# schematic_01.net
KiCad netlist of a schematic drawn in Altium Designer
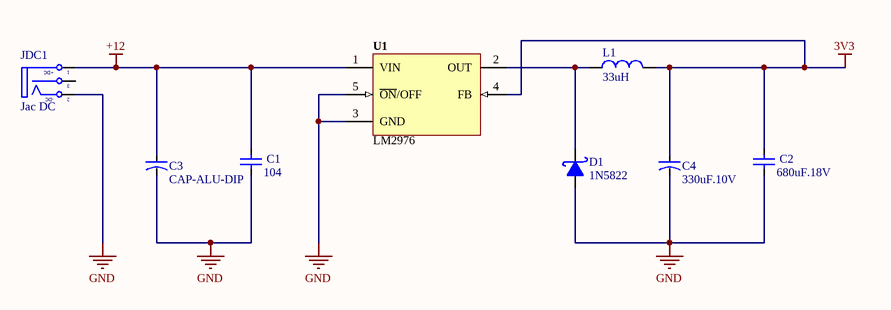
[diagram p0: schematic_01.SchDoc]

(export (version "E")
  (design (tool "Eeschema 10.0.6"))
  (components
    (comp (ref "C1")
      (value "104")
      (footprint "CAP_0805")
      (description "Capacitor")
      (fields (field (name "PUBLISHER") "Altium Limited"))
      (libsource (lib "My-Library") (part "CapSMD"))
    )
    (comp (ref "C2")
      (value "680uF.18V")
      (footprint "CAP_0805")
      (description "Capacitor")
      (fields (field (name "PUBLISHER") "Altium Limited"))
      (libsource (lib "My-Library") (part "CapSMD"))
    )
    (comp (ref "C3")
      (value "CAP-ALU-DIP")
      (footprint "CA-ALU-2.54")
      (description "Capacitor (Semiconductor SIM Model)")
      (fields (field (name "PUBLISHER") "Altium Limited"))
      (libsource (lib "My-Library") (part "CAP-ALU-DIP"))
    )
    (comp (ref "C4")
      (value "330uF.10V")
      (footprint "CA-ALU-2.54")
      (description "Capacitor (Semiconductor SIM Model)")
      (fields (field (name "PUBLISHER") "Altium Limited"))
      (libsource (lib "My-Library") (part "CAP-ALU-DIP"))
    )
    (comp (ref "D1")
      (value "1N5822")
      (footprint "SMA")
      (description "Schottky Rectifiers")
      (libsource (lib "My-Library") (part "1N5822"))
    )
    (comp (ref "JDC1")
      (value "Jac DC")
      (footprint "DC-IN")
      (description "Jac DC input")
      (libsource (lib "My-Library") (part "DCIN"))
    )
    (comp (ref "L1")
      (value "33uH")
      (footprint "L-SMD-M-12x10")
      (description "Inductor")
      (libsource (lib "My-Library") (part "Inductor"))
    )
    (comp (ref "U1") (value "LM2976") (footprint "TO263-5") (libsource (lib "My-Library") (part "LM2596")))
  )
  (nets
    (net (code "1") (name "+12") (class "Default")
      (node (ref "C1") (pin "2") (pinfunction "2_2") (pintype "passive"))
      (node (ref "C3") (pin "1") (pinfunction "1_1") (pintype "passive"))
      (node (ref "JDC1") (pin "1") (pinfunction "T_1") (pintype "passive"))
      (node (ref "U1") (pin "1") (pinfunction "VIN_1") (pintype "power_in"))
    )
    (net (code "2") (name "3V3") (class "Default")
      (node (ref "C2") (pin "2") (pinfunction "2_2") (pintype "passive"))
      (node (ref "C4") (pin "1") (pinfunction "1_1") (pintype "passive"))
      (node (ref "L1") (pin "2") (pinfunction "2_2") (pintype "passive"))
      (node (ref "U1") (pin "4") (pinfunction "FB_4") (pintype "input"))
    )
    (net (code "3") (name "GND") (class "Default")
      (node (ref "C1") (pin "1") (pinfunction "1_1") (pintype "passive"))
      (node (ref "C2") (pin "1") (pinfunction "1_1") (pintype "passive"))
      (node (ref "C3") (pin "2") (pinfunction "2_2") (pintype "passive"))
      (node (ref "C4") (pin "2") (pinfunction "2_2") (pintype "passive"))
      (node (ref "D1") (pin "1") (pinfunction "A_1") (pintype "passive"))
      (node (ref "JDC1") (pin "2") (pinfunction "TN_2") (pintype "passive"))
      (node (ref "U1") (pin "3") (pinfunction "GND_3") (pintype "power_in"))
      (node (ref "U1") (pin "5") (pinfunction "~{ON}/OFF_5") (pintype "input"))
    )
    (net (code "4") (name "Net-(D1-K)") (class "Default")
      (node (ref "D1") (pin "2") (pinfunction "K_2") (pintype "passive"))
      (node (ref "L1") (pin "1") (pinfunction "1_1") (pintype "passive"))
      (node (ref "U1") (pin "2") (pinfunction "OUT_2") (pintype "power_in"))
    )
    (net (code "5") (name "unconnected-(JDC1-S-Pad3)") (class "Default")
      (node (ref "JDC1") (pin "3") (pinfunction "S_3") (pintype "power_in"))
    )
  )
)
